# CHM_CPU_FPGA_ADC.net
KiCad netlist of a schematic drawn in Altium Designer
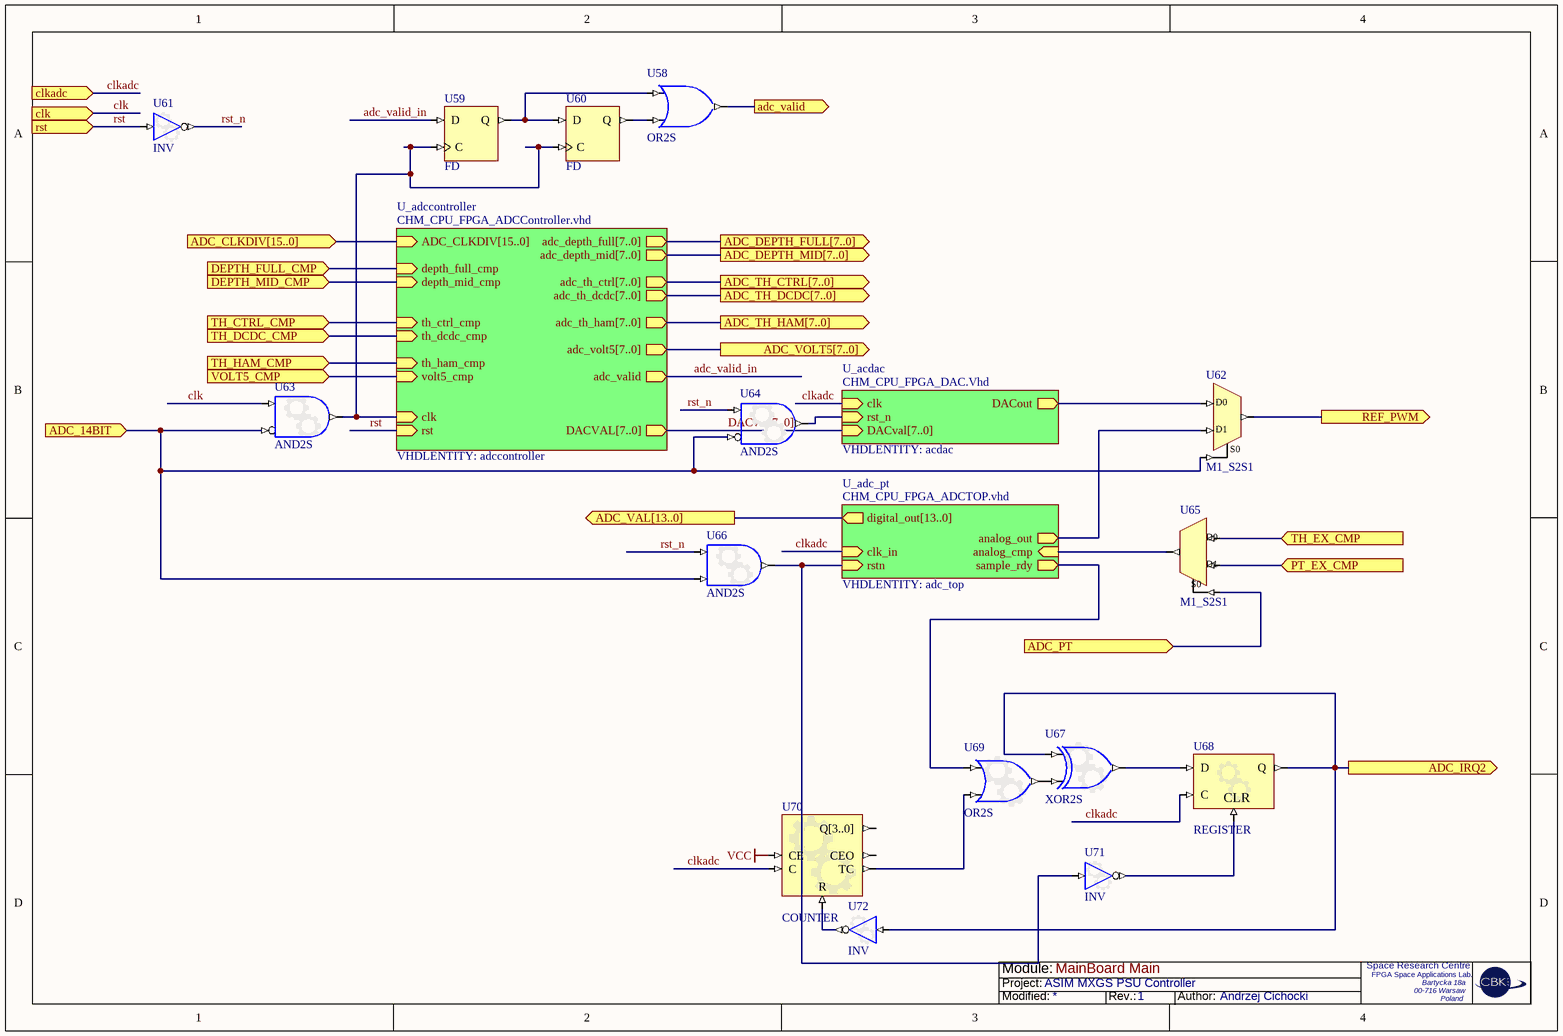
[diagram p0: CHM_CPU_FPGA_ADC.SchDoc]

(export (version "E")
  (design (tool "Eeschema 10.0.6"))
  (components
    (comp (ref "U58")
      (value "OR2S")
      (description "2-Input OR Gate, Single Pin Version")
      (fields (field (name "PUBLISHER") "Altium Limited"))
      (libsource (lib "FPGA Generic") (part "OR2S"))
    )
    (comp (ref "U59")
      (value "FD")
      (description "D-Type Flip-Flop")
      (fields (field (name "PUBLISHER") "Altium Limited"))
      (libsource (lib "FPGA Generic") (part "FD"))
    )
    (comp (ref "U60")
      (value "FD")
      (description "D-Type Flip-Flop")
      (fields (field (name "PUBLISHER") "Altium Limited"))
      (libsource (lib "FPGA Generic") (part "FD"))
    )
    (comp (ref "U61")
      (value "INV")
      (description "Configurable Inverter")
      (fields (field (name "PUBLISHER") "Altium Limited"))
      (libsource (lib "FPGA Configurable Generic") (part "INV"))
    )
    (comp (ref "U62")
      (value "M1_S2S1")
      (description "2x1-Single Wire to 1x1-Single Wire Multiplexer")
      (fields (field (name "PUBLISHER") "Altium Limited"))
      (libsource (lib "FPGA Generic") (part "M1_S2S1"))
    )
    (comp (ref "U63")
      (value "AND2S")
      (description "Configurable Generic Gate")
      (fields (field (name "PUBLISHER") "Altium Limited"))
      (libsource (lib "") (part "GATE_2"))
    )
    (comp (ref "U64")
      (value "AND2S")
      (description "Configurable Generic Gate")
      (fields (field (name "PUBLISHER") "Altium Limited"))
      (libsource (lib "") (part "GATE_2"))
    )
    (comp (ref "U65")
      (value "M1_S2S1")
      (description "2x1-Single Wire to 1x1-Single Wire Multiplexer")
      (fields (field (name "PUBLISHER") "Altium Limited"))
      (libsource (lib "FPGA Generic") (part "M1_S2S1"))
    )
    (comp (ref "U66")
      (value "AND2S")
      (description "Configurable Generic Gate")
      (fields (field (name "PUBLISHER") "Altium Limited"))
      (libsource (lib "") (part "GATE_2"))
    )
    (comp (ref "U67")
      (value "XOR2S")
      (description "Configurable Generic Gate")
      (fields (field (name "PUBLISHER") "Altium Limited"))
      (libsource (lib "") (part "GATE_1"))
    )
    (comp (ref "U68")
      (value "REGISTER")
      (description "Configurable Register")
      (fields (field (name "PUBLISHER") "Altium Limited"))
      (libsource (lib "FPGA Configurable Generic") (part "REGISTER"))
    )
    (comp (ref "U69")
      (value "OR2S")
      (description "Configurable Generic Gate")
      (fields (field (name "PUBLISHER") "Altium Limited"))
      (libsource (lib "FPGA Configurable Generic") (part "GATE"))
    )
    (comp (ref "U70")
      (value "COUNTER")
      (description "Configurable Counter")
      (fields (field (name "PUBLISHER") "Altium Limited"))
      (libsource (lib "FPGA Configurable Generic") (part "COUNTER"))
    )
    (comp (ref "U71")
      (value "INV")
      (description "Configurable Inverter")
      (fields (field (name "PUBLISHER") "Altium Limited"))
      (libsource (lib "FPGA Configurable Generic") (part "INV"))
    )
    (comp (ref "U72")
      (value "INV")
      (description "Configurable Inverter")
      (fields (field (name "PUBLISHER") "Altium Limited"))
      (libsource (lib "FPGA Configurable Generic") (part "INV"))
    )
  )
  (nets
    (net (code "87") (name "/ADC_14BIT") (class "Default")
      (node (ref "U62") (pin "S0") (pinfunction "S0_S0") (pintype "input"))
      (node (ref "U63") (pin "I1") (pinfunction "I1_I1") (pintype "input"))
      (node (ref "U64") (pin "I1") (pinfunction "I1_I1") (pintype "input"))
      (node (ref "U66") (pin "I1") (pinfunction "I1_I1") (pintype "input"))
    )
    (net (code "91") (name "/ADC_IRQ2") (class "Default")
      (node (ref "U67") (pin "I0") (pinfunction "I0_I0") (pintype "input"))
      (node (ref "U68") (pin "Q") (pinfunction "Q_Q") (pintype "output"))
      (node (ref "U72") (pin "I") (pinfunction "I_I") (pintype "input"))
    )
    (net (code "92") (name "/ADC_PT") (class "Default")
      (node (ref "U65") (pin "S0") (pinfunction "S0_S0") (pintype "input"))
    )
    (net (code "98") (name "/DACout") (class "Default")
      (node (ref "U62") (pin "D0") (pinfunction "D0_D0") (pintype "input"))
    )
    (net (code "102") (name "/PT_EX_CMP") (class "Default")
      (node (ref "U65") (pin "D1") (pinfunction "D1_D1") (pintype "input"))
    )
    (net (code "103") (name "/REF_PWM") (class "Default")
      (node (ref "U62") (pin "O") (pinfunction "O_O") (pintype "output"))
    )
    (net (code "106") (name "/TH_EX_CMP") (class "Default")
      (node (ref "U65") (pin "D0") (pinfunction "D0_D0") (pintype "input"))
    )
    (net (code "109") (name "/adc_valid") (class "Default")
      (node (ref "U58") (pin "O") (pinfunction "O_O") (pintype "output"))
    )
    (net (code "110") (name "/adc_valid_in") (class "Default")
      (node (ref "U59") (pin "D") (pinfunction "D_D") (pintype "input"))
    )
    (net (code "111") (name "/analog_cmp") (class "Default")
      (node (ref "U65") (pin "O") (pinfunction "O_O") (pintype "output"))
    )
    (net (code "112") (name "/analog_out") (class "Default")
      (node (ref "U62") (pin "D1") (pinfunction "D1_D1") (pintype "input"))
    )
    (net (code "113") (name "/clk") (class "Default")
      (node (ref "U63") (pin "I0") (pinfunction "I0_I0") (pintype "input"))
    )
    (net (code "114") (name "/clk_1") (class "Default")
      (node (ref "U59") (pin "C") (pinfunction "C_C") (pintype "input"))
      (node (ref "U60") (pin "C") (pinfunction "C_C") (pintype "input"))
      (node (ref "U63") (pin "O") (pinfunction "O_O") (pintype "output"))
    )
    (net (code "115") (name "/clkadc") (class "Default")
      (node (ref "U68") (pin "C") (pinfunction "C_C") (pintype "input"))
      (node (ref "U70") (pin "C") (pinfunction "C_C") (pintype "input"))
    )
    (net (code "116") (name "/rst") (class "Default")
      (node (ref "U61") (pin "I") (pinfunction "I_I") (pintype "input"))
    )
    (net (code "117") (name "/rst_n") (class "Default")
      (node (ref "U61") (pin "O") (pinfunction "O_O") (pintype "output"))
      (node (ref "U64") (pin "I0") (pinfunction "I0_I0") (pintype "input"))
      (node (ref "U66") (pin "I0") (pinfunction "I0_I0") (pintype "input"))
    )
    (net (code "118") (name "/rst_n_1") (class "Default")
      (node (ref "U64") (pin "O") (pinfunction "O_O") (pintype "output"))
    )
    (net (code "120") (name "/sample_rdy") (class "Default")
      (node (ref "U69") (pin "I0") (pinfunction "I0_I0") (pintype "input"))
    )
    (net (code "121") (name "Net-(U58-PadI0)") (class "Default")
      (node (ref "U58") (pin "I0") (pinfunction "I0_I0") (pintype "input"))
      (node (ref "U59") (pin "Q") (pinfunction "Q_Q") (pintype "output"))
      (node (ref "U60") (pin "D") (pinfunction "D_D") (pintype "input"))
    )
    (net (code "122") (name "Net-(U58-PadI1)") (class "Default")
      (node (ref "U58") (pin "I1") (pinfunction "I1_I1") (pintype "input"))
      (node (ref "U60") (pin "Q") (pinfunction "Q_Q") (pintype "output"))
    )
    (net (code "123") (name "Net-(U66-PadO)") (class "Default")
      (node (ref "U66") (pin "O") (pinfunction "O_O") (pintype "output"))
      (node (ref "U71") (pin "I") (pinfunction "I_I") (pintype "input"))
    )
    (net (code "124") (name "Net-(U67-PadI1)") (class "Default")
      (node (ref "U67") (pin "I1") (pinfunction "I1_I1") (pintype "input"))
      (node (ref "U69") (pin "O") (pinfunction "O_O") (pintype "output"))
    )
    (net (code "125") (name "Net-(U67-PadO)") (class "Default")
      (node (ref "U67") (pin "O") (pinfunction "O_O") (pintype "output"))
      (node (ref "U68") (pin "D") (pinfunction "D_D") (pintype "input"))
    )
    (net (code "126") (name "Net-(U68-PadCLR)") (class "Default")
      (node (ref "U68") (pin "CLR") (pinfunction "CLR_CLR") (pintype "input"))
      (node (ref "U71") (pin "O") (pinfunction "O_O") (pintype "output"))
    )
    (net (code "127") (name "Net-(U69-PadI1)") (class "Default")
      (node (ref "U69") (pin "I1") (pinfunction "I1_I1") (pintype "input"))
      (node (ref "U70") (pin "TC") (pinfunction "TC_TC") (pintype "output"))
    )
    (net (code "128") (name "Net-(U70-PadR)") (class "Default")
      (node (ref "U70") (pin "R") (pinfunction "R_R") (pintype "input"))
      (node (ref "U72") (pin "O") (pinfunction "O_O") (pintype "output"))
    )
    (net (code "129") (name "VCC") (class "Default")
      (node (ref "U70") (pin "CE") (pinfunction "CE_CE") (pintype "input"))
    )
    (net (code "130") (name "unconnected-(U70-PadCEO)") (class "Default")
      (node (ref "U70") (pin "CEO") (pinfunction "CEO_CEO") (pintype "output"))
    )
    (net (code "131") (name "unconnected-(U70-PadQ[3..0])") (class "Default")
      (node (ref "U70") (pin "Q[3..0]") (pinfunction "Q[3..0]_Q[3..0]") (pintype "output"))
    )
  )
)
